# Connector.net
KiCad netlist of a schematic drawn in Altium Designer
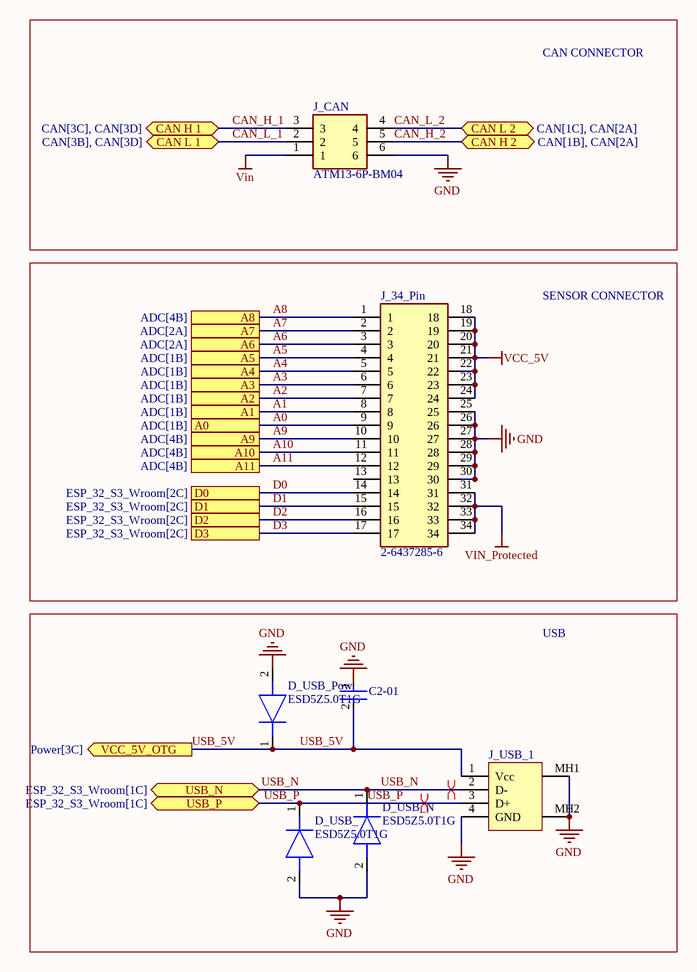
[diagram p0: Connector.SchDoc]

(export (version "E")
  (design (tool "Eeschema 10.0.6"))
  (components
    (comp (ref "C2-01")
      (value "GRM21BZ71E106KE15L")
      (footprint "FP-GRM21B-0_2-e0_2_0_7-IPC_B")
      (description "Chip Multilayer Ceramic Capacitors for General Purpose, 0805, 10uF, X7R, 15%, 10%, 25V")
      (libsource (lib "Altium Content Vault") (part "b4654b650e69147ec39a6b967a45e02"))
    )
    (comp (ref "D_USB_")
      (value "ESD5Z5.0T1G")
      (footprint "SamacSys:SODFL1608X70N")
      (description "Diode")
      (fields (field (name "MOUSER PART NUMBER") "863-ESD5Z5.0T1G"))
      (libsource (lib "*") (part "ESD5Z5.0T1G"))
    )
    (comp (ref "D_USB_N")
      (value "ESD5Z5.0T1G")
      (footprint "SamacSys:SODFL1608X70N")
      (description "Diode")
      (fields (field (name "MOUSER PART NUMBER") "863-ESD5Z5.0T1G"))
      (libsource (lib "*") (part "ESD5Z5.0T1G"))
    )
    (comp (ref "D_USB_Pow")
      (value "ESD5Z5.0T1G")
      (footprint "SamacSys:SODFL1608X70N")
      (description "Diode")
      (fields (field (name "MOUSER PART NUMBER") "863-ESD5Z5.0T1G"))
      (libsource (lib "*") (part "ESD5Z5.0T1G"))
    )
    (comp (ref "J_34_Pin")
      (value "2-6437285-6")
      (footprint "SamacSys:264372856")
      (description "Connector")
      (fields (field (name "MOUSER PART NUMBER") "571-2-6437285-6"))
      (libsource (lib "*") (part "2-6437285-6"))
    )
    (comp (ref "J_CAN")
      (value "ATM13-6P-BM04")
      (footprint "ATM136PBM04")
      (description "Connector")
      (fields (field (name "MOUSER PART NUMBER") "654-ATM13-6P-BM04"))
      (libsource (lib "Americas- Grizzlies Racing- Oakland University") (part "ATM13-6P-BM04"))
    )
    (comp (ref "J_USB_1")
      (value "61729-0010BLF")
      (footprint "FCI-61729-0010BLF-6_V")
      (description "Single USB 2.0, B Type, Right Angle Jack, Through Hole, RoHS, Tube")
      (fields (field (name "MANUFACTURER") "FCI Electronics"))
      (libsource (lib "Altium Content Vault") (part "FCI-CN-1F-R6"))
    )
  )
  (nets
    (net (code "1") (name "/A0") (class "Default")
      (node (ref "J_34_Pin") (pin "9") (pinfunction "9_9") (pintype "passive"))
    )
    (net (code "2") (name "/A1") (class "Default")
      (node (ref "J_34_Pin") (pin "8") (pinfunction "8_8") (pintype "passive"))
    )
    (net (code "3") (name "/A2") (class "Default")
      (node (ref "J_34_Pin") (pin "7") (pinfunction "7_7") (pintype "passive"))
    )
    (net (code "4") (name "/A3") (class "Default")
      (node (ref "J_34_Pin") (pin "6") (pinfunction "6_6") (pintype "passive"))
    )
    (net (code "5") (name "/A4") (class "Default")
      (node (ref "J_34_Pin") (pin "5") (pinfunction "5_5") (pintype "passive"))
    )
    (net (code "6") (name "/A5") (class "Default")
      (node (ref "J_34_Pin") (pin "4") (pinfunction "4_4") (pintype "passive"))
    )
    (net (code "7") (name "/A6") (class "Default")
      (node (ref "J_34_Pin") (pin "3") (pinfunction "3_3") (pintype "passive"))
    )
    (net (code "8") (name "/A7") (class "Default")
      (node (ref "J_34_Pin") (pin "2") (pinfunction "2_2") (pintype "passive"))
    )
    (net (code "9") (name "/A8") (class "Default")
      (node (ref "J_34_Pin") (pin "1") (pinfunction "1_1") (pintype "passive"))
    )
    (net (code "10") (name "/A9") (class "Default")
      (node (ref "J_34_Pin") (pin "10") (pinfunction "10_10") (pintype "passive"))
    )
    (net (code "11") (name "/A10") (class "Default")
      (node (ref "J_34_Pin") (pin "11") (pinfunction "11_11") (pintype "passive"))
    )
    (net (code "12") (name "/A11") (class "Default")
      (node (ref "J_34_Pin") (pin "12") (pinfunction "12_12") (pintype "passive"))
    )
    (net (code "13") (name "/CAN_H_1") (class "Default")
      (node (ref "J_CAN") (pin "3") (pinfunction "3_3") (pintype "passive"))
    )
    (net (code "14") (name "/CAN_H_2") (class "Default")
      (node (ref "J_CAN") (pin "5") (pinfunction "5_5") (pintype "passive"))
    )
    (net (code "15") (name "/CAN_L_1") (class "Default")
      (node (ref "J_CAN") (pin "2") (pinfunction "2_2") (pintype "passive"))
    )
    (net (code "16") (name "/CAN_L_2") (class "Default")
      (node (ref "J_CAN") (pin "4") (pinfunction "4_4") (pintype "passive"))
    )
    (net (code "17") (name "/D0") (class "Default")
      (node (ref "J_34_Pin") (pin "14") (pinfunction "14_14") (pintype "passive"))
    )
    (net (code "18") (name "/D1") (class "Default")
      (node (ref "J_34_Pin") (pin "15") (pinfunction "15_15") (pintype "passive"))
    )
    (net (code "19") (name "/D2") (class "Default")
      (node (ref "J_34_Pin") (pin "16") (pinfunction "16_16") (pintype "passive"))
    )
    (net (code "20") (name "/D3") (class "Default")
      (node (ref "J_34_Pin") (pin "17") (pinfunction "17_17") (pintype "passive"))
    )
    (net (code "21") (name "/USB_5V") (class "Default")
      (node (ref "C2-01") (pin "2") (pinfunction "2_2") (pintype "passive"))
      (node (ref "D_USB_Pow") (pin "1") (pinfunction "K_1") (pintype "passive"))
      (node (ref "J_USB_1") (pin "1") (pinfunction "Vcc_1") (pintype "passive"))
    )
    (net (code "22") (name "/USB_N") (class "Default")
      (node (ref "D_USB_N") (pin "1") (pinfunction "K_1") (pintype "passive"))
      (node (ref "J_USB_1") (pin "2") (pinfunction "D-_2") (pintype "passive"))
    )
    (net (code "23") (name "/USB_P") (class "Default")
      (node (ref "D_USB_") (pin "1") (pinfunction "K_1") (pintype "passive"))
      (node (ref "J_USB_1") (pin "3") (pinfunction "D+_3") (pintype "passive"))
    )
    (net (code "24") (name "GND") (class "Default")
      (node (ref "C2-01") (pin "1") (pinfunction "1_1") (pintype "passive"))
      (node (ref "D_USB_") (pin "2") (pinfunction "A_2") (pintype "passive"))
      (node (ref "D_USB_N") (pin "2") (pinfunction "A_2") (pintype "passive"))
      (node (ref "D_USB_Pow") (pin "2") (pinfunction "A_2") (pintype "passive"))
      (node (ref "J_34_Pin") (pin "25") (pinfunction "25_25") (pintype "passive"))
      (node (ref "J_34_Pin") (pin "26") (pinfunction "26_26") (pintype "passive"))
      (node (ref "J_34_Pin") (pin "27") (pinfunction "27_27") (pintype "passive"))
      (node (ref "J_34_Pin") (pin "28") (pinfunction "28_28") (pintype "passive"))
      (node (ref "J_34_Pin") (pin "29") (pinfunction "29_29") (pintype "passive"))
      (node (ref "J_34_Pin") (pin "30") (pinfunction "30_30") (pintype "passive"))
      (node (ref "J_CAN") (pin "6") (pinfunction "6_6") (pintype "passive"))
      (node (ref "J_USB_1") (pin "4") (pinfunction "GND_4") (pintype "passive"))
      (node (ref "J_USB_1") (pin "MH1") (pinfunction "MH1_MH1") (pintype "passive"))
      (node (ref "J_USB_1") (pin "MH2") (pinfunction "MH2_MH2") (pintype "passive"))
    )
    (net (code "25") (name "VCC_5V") (class "Default")
      (node (ref "J_34_Pin") (pin "18") (pinfunction "18_18") (pintype "passive"))
      (node (ref "J_34_Pin") (pin "19") (pinfunction "19_19") (pintype "passive"))
      (node (ref "J_34_Pin") (pin "20") (pinfunction "20_20") (pintype "passive"))
      (node (ref "J_34_Pin") (pin "21") (pinfunction "21_21") (pintype "passive"))
      (node (ref "J_34_Pin") (pin "22") (pinfunction "22_22") (pintype "passive"))
      (node (ref "J_34_Pin") (pin "23") (pinfunction "23_23") (pintype "passive"))
      (node (ref "J_34_Pin") (pin "24") (pinfunction "24_24") (pintype "passive"))
    )
    (net (code "26") (name "VIN_Protected") (class "Default")
      (node (ref "J_34_Pin") (pin "31") (pinfunction "31_31") (pintype "passive"))
      (node (ref "J_34_Pin") (pin "32") (pinfunction "32_32") (pintype "passive"))
      (node (ref "J_34_Pin") (pin "33") (pinfunction "33_33") (pintype "passive"))
      (node (ref "J_34_Pin") (pin "34") (pinfunction "34_34") (pintype "passive"))
    )
    (net (code "27") (name "Vin") (class "Default")
      (node (ref "J_CAN") (pin "1") (pinfunction "1_1") (pintype "passive"))
    )
    (net (code "28") (name "unconnected-(J_34_Pin-Pad13)") (class "Default")
      (node (ref "J_34_Pin") (pin "13") (pinfunction "13_13") (pintype "passive"))
    )
  )
)
